# PDB.net
KiCad netlist of a schematic drawn in EAGLE
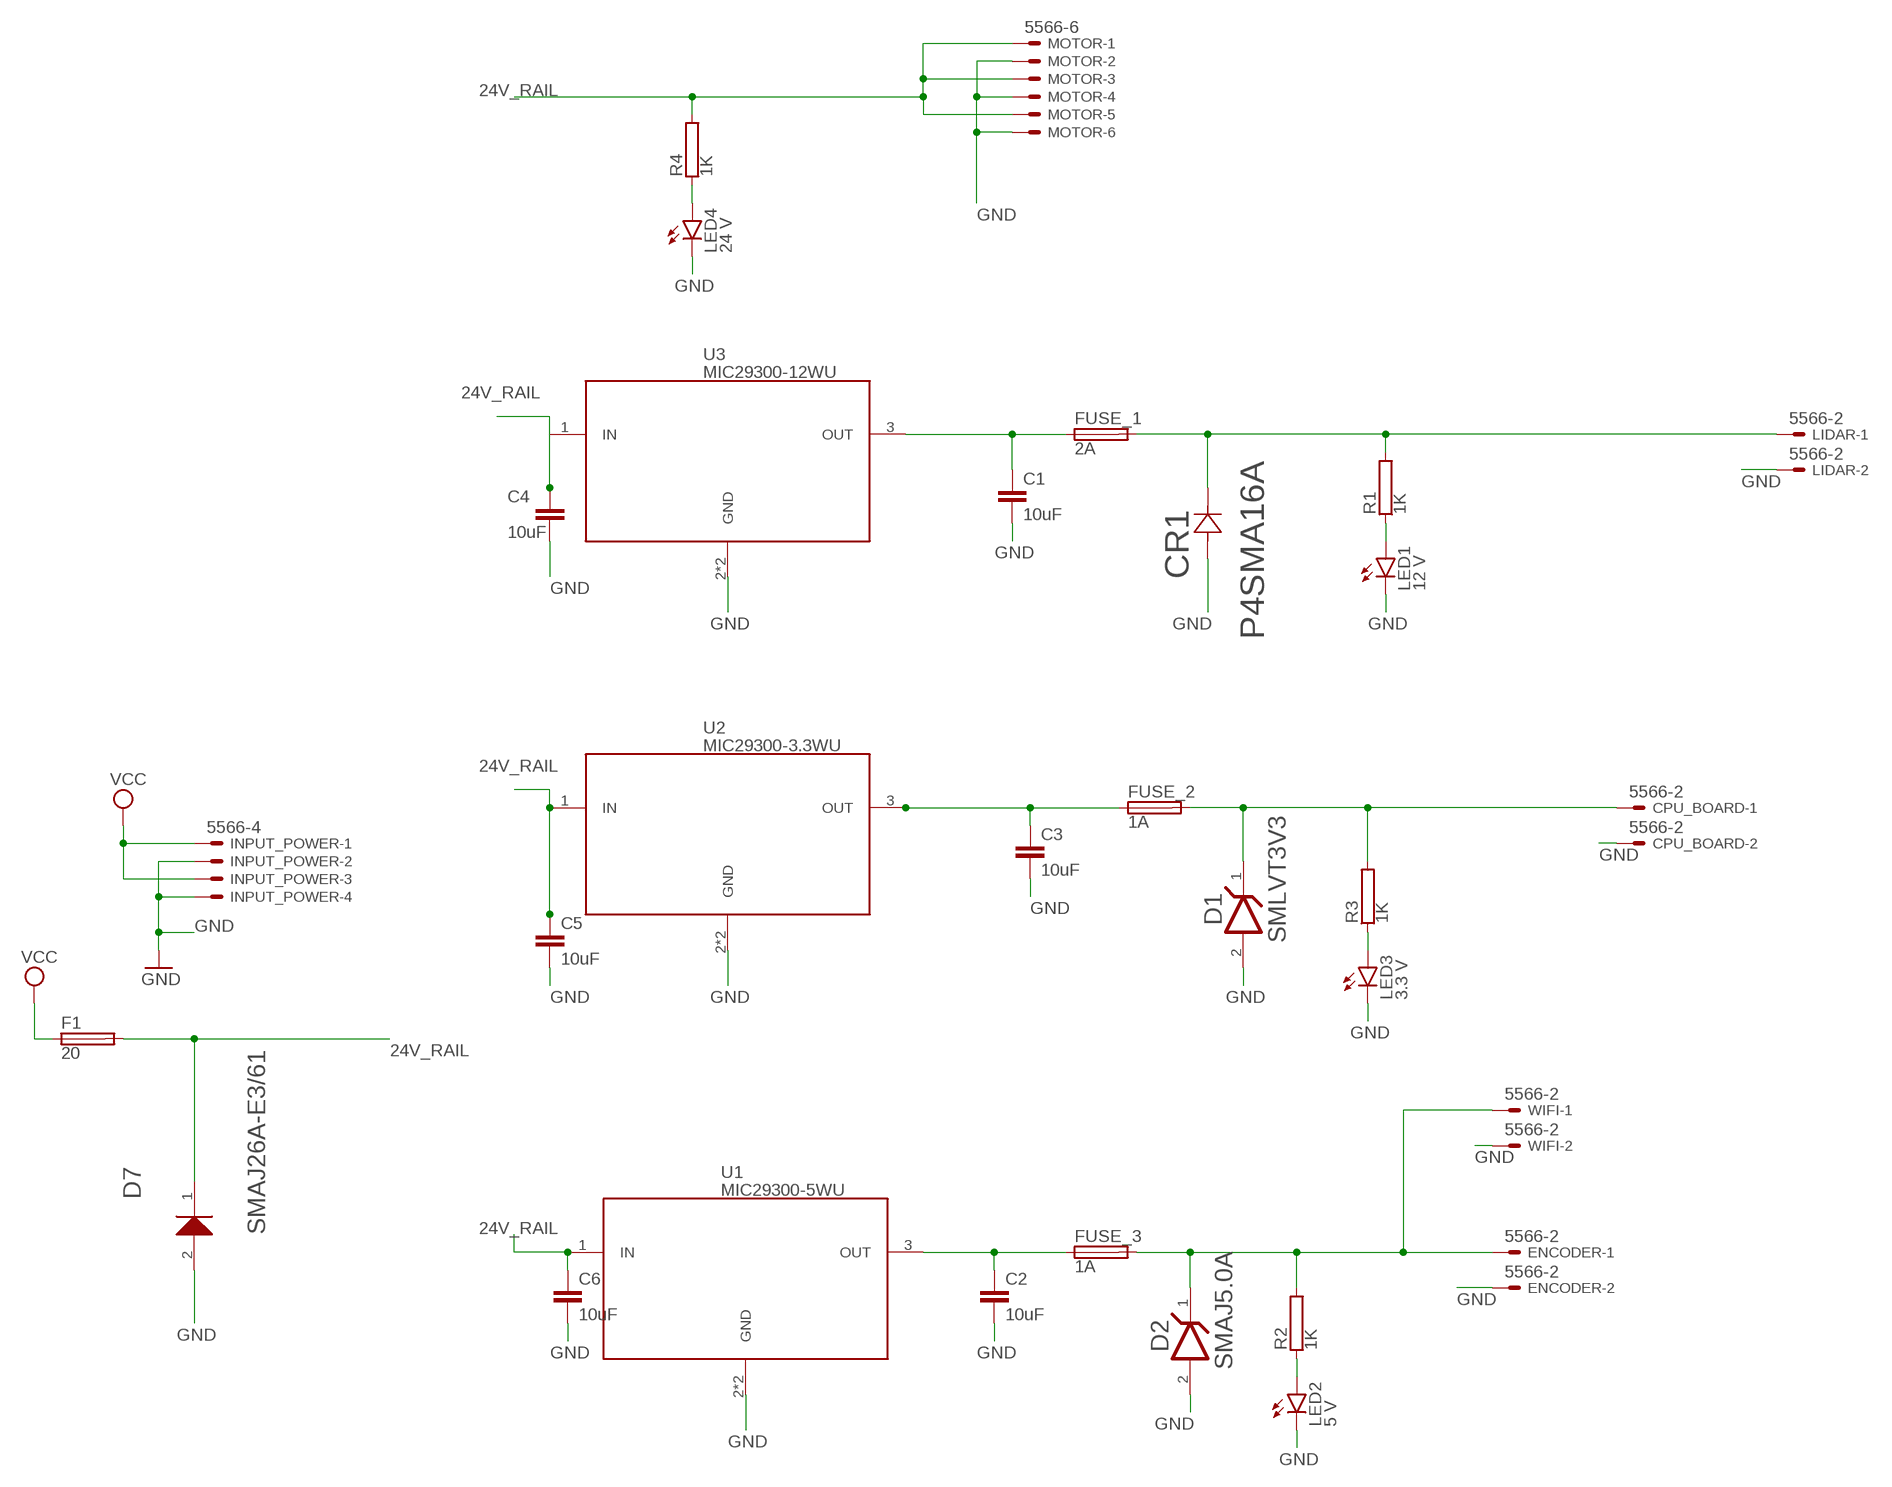
[diagram p0: schematic, sheet 1]

(export (version "E")
  (design (tool "Eeschema 10.0.6"))
  (components
    (comp (ref "C1")
      (value "10uF")
      (footprint "eagle-import:C2.5-2")
      (libsource (lib "eagle-import") (part "C2.5/2"))
    )
    (comp (ref "C2")
      (value "10uF")
      (footprint "eagle-import:C2.5-2")
      (libsource (lib "eagle-import") (part "C2.5/2"))
    )
    (comp (ref "C3")
      (value "10uF")
      (footprint "eagle-import:C2.5-2")
      (libsource (lib "eagle-import") (part "C2.5/2"))
    )
    (comp (ref "C4")
      (value "10uF")
      (footprint "eagle-import:C2.5-2")
      (libsource (lib "eagle-import") (part "C2.5/2"))
    )
    (comp (ref "C5")
      (value "10uF")
      (footprint "eagle-import:C2.5-2")
      (libsource (lib "eagle-import") (part "C2.5/2"))
    )
    (comp (ref "C6")
      (value "10uF")
      (footprint "eagle-import:C2.5-2")
      (libsource (lib "eagle-import") (part "C2.5/2"))
    )
    (comp (ref "CPU_BOARD")
      (value "5566-2")
      (footprint "eagle-import:5566-2")
      (fields (field (name "MF") "MOLEX"))
      (libsource (lib "eagle-import") (part "5566-2"))
    )
    (comp (ref "CR1")
      (value "P4SMA16A")
      (footprint "eagle-import:P4SMASERIES_LTF")
      (fields (field (name "COPYRIGHT") "Copyright (C) 2022 Ultra Librarian. All rights reserved."))
      (libsource (lib "eagle-import") (part "P4SMA16A"))
    )
    (comp (ref "D1")
      (value "STMICROELECTRONICS_SMLVT3V3STMICROELECTRONICS_SMLVT3V3_0_0")
      (footprint "eagle-import:STMICROELECTRONICS_SMLVT3V3_0")
      (fields
        (field (name "DIGIKEY_PART_NUMBER") "497-2496-1-ND")
        (field (name "MF") "STMicroelectronics")
        (field (name "MOUSER_PART_NUMBER") "511-SMLVT3V3")
      )
      (libsource (lib "eagle-import") (part "STMICROELECTRONICS_SMLVT3V3STMICROELECTRONICS_SMLVT3V3_0_0"))
    )
    (comp (ref "D2")
      (value "LITTELFUSE_INC._SMAJ5.0ALITTELFUSE_INC._SMAJ5.0A_0_0")
      (footprint "eagle-import:LITTELFUSE_INC._SMAJ5.0A_0")
      (fields
        (field (name "DIGIKEY_PART_NUMBER") "SMAJ5.0ALFCT-ND")
        (field (name "MF") "Littelfuse Inc.")
        (field (name "MOUSER_PART_NUMBER") "576-SMAJ5.0A")
      )
      (libsource (lib "eagle-import") (part "LITTELFUSE_INC._SMAJ5.0ALITTELFUSE_INC._SMAJ5.0A_0_0"))
    )
    (comp (ref "D7")
      (value "VISHAY_SEMICONDUCTOR_SMAJ26A-E3-61VISHAY_SEMICONDUCTOR_SMAJ26A-E3-61_0_0")
      (footprint "eagle-import:VISHAY_SEMICONDUCTOR_SMAJ26A-E3-61_0")
      (fields (field (name "MF") "Vishay Semiconductor") (field (name "MPN") "SMAJ26A-E3/61"))
      (libsource (lib "eagle-import") (part "VISHAY_SEMICONDUCTOR_SMAJ26A-E3-61VISHAY_SEMICONDUCTOR_SMAJ26A-E3-61_0_0"))
    )
    (comp (ref "ENCODER")
      (value "5566-2")
      (footprint "eagle-import:5566-2")
      (fields (field (name "MF") "MOLEX"))
      (libsource (lib "eagle-import") (part "5566-2"))
    )
    (comp (ref "F1")
      (value "20")
      (footprint "eagle-import:TE5")
      (libsource (lib "eagle-import") (part "TE5"))
    )
    (comp (ref "FUSE_1")
      (value "2A")
      (footprint "eagle-import:TE5")
      (libsource (lib "eagle-import") (part "TE5"))
    )
    (comp (ref "FUSE_2")
      (value "1A")
      (footprint "eagle-import:TE5")
      (libsource (lib "eagle-import") (part "TE5"))
    )
    (comp (ref "FUSE_3")
      (value "1A")
      (footprint "eagle-import:TE5")
      (libsource (lib "eagle-import") (part "TE5"))
    )
    (comp (ref "INPUT_POWER")
      (value "5566-4")
      (footprint "eagle-import:5566-4")
      (fields (field (name "MF") "MOLEX"))
      (libsource (lib "eagle-import") (part "5566-4"))
    )
    (comp (ref "LED1")
      (value "12 V")
      (footprint "eagle-import:CHIPLED_0805")
      (libsource (lib "eagle-import") (part "LEDCHIPLED_0805"))
    )
    (comp (ref "LED2")
      (value "5 V")
      (footprint "eagle-import:CHIPLED_0805")
      (libsource (lib "eagle-import") (part "LEDCHIPLED_0805"))
    )
    (comp (ref "LED3")
      (value "3.3 V")
      (footprint "eagle-import:CHIPLED_0805")
      (libsource (lib "eagle-import") (part "LEDCHIPLED_0805"))
    )
    (comp (ref "LED4")
      (value "24 V")
      (footprint "eagle-import:CHIPLED_0805")
      (libsource (lib "eagle-import") (part "LEDCHIPLED_0805"))
    )
    (comp (ref "LIDAR")
      (value "5566-2")
      (footprint "eagle-import:5566-2")
      (fields (field (name "MF") "MOLEX"))
      (libsource (lib "eagle-import") (part "5566-2"))
    )
    (comp (ref "MOTOR")
      (value "5566-6")
      (footprint "eagle-import:5566-6")
      (fields (field (name "MF") "MOLEX") (field (name "MPN") "95566-61002"))
      (libsource (lib "eagle-import") (part "5566-6"))
    )
    (comp (ref "R1")
      (value "1K")
      (footprint "eagle-import:TO-247-2V")
      (libsource (lib "eagle-import") (part "RMG100-V"))
    )
    (comp (ref "R2")
      (value "1K")
      (footprint "eagle-import:TO-247-2V")
      (libsource (lib "eagle-import") (part "RMG100-V"))
    )
    (comp (ref "R3")
      (value "1K")
      (footprint "eagle-import:TO-247-2V")
      (libsource (lib "eagle-import") (part "RMG100-V"))
    )
    (comp (ref "R4")
      (value "1K")
      (footprint "eagle-import:TO-247-2V")
      (libsource (lib "eagle-import") (part "RMG100-V"))
    )
    (comp (ref "U1")
      (value "MIC29300-5WU")
      (footprint "eagle-import:TO263")
      (fields (field (name "MF") "Microchip Technology"))
      (libsource (lib "eagle-import") (part "MIC29300-5WU"))
    )
    (comp (ref "U2")
      (value "MIC29300-3.3WU")
      (footprint "eagle-import:TO263")
      (fields (field (name "MF") "Microchip Technology"))
      (libsource (lib "eagle-import") (part "MIC29300-3.3WU"))
    )
    (comp (ref "U3")
      (value "MIC29300-12WU")
      (footprint "eagle-import:TO263")
      (fields (field (name "MF") "Microchip Technology"))
      (libsource (lib "eagle-import") (part "MIC29300-12WU"))
    )
    (comp (ref "WIFI")
      (value "5566-2")
      (footprint "eagle-import:5566-2")
      (fields (field (name "MF") "MOLEX"))
      (libsource (lib "eagle-import") (part "5566-2"))
    )
  )
  (nets
    (net (code "1") (name "/24V_RAIL") (class "Default")
      (node (ref "C4") (pin "1") (pinfunction "1_1") (pintype "passive"))
      (node (ref "C5") (pin "1") (pinfunction "1_1") (pintype "passive"))
      (node (ref "C6") (pin "1") (pinfunction "1_1") (pintype "passive"))
      (node (ref "D7") (pin "1") (pinfunction "K_1") (pintype "passive"))
      (node (ref "F1") (pin "2") (pinfunction "2_2") (pintype "passive"))
      (node (ref "MOTOR") (pin "1") (pinfunction "S_1") (pintype "passive"))
      (node (ref "MOTOR") (pin "3") (pinfunction "S_3") (pintype "passive"))
      (node (ref "MOTOR") (pin "5") (pinfunction "S_5") (pintype "passive"))
      (node (ref "R4") (pin "2") (pinfunction "2_2") (pintype "passive"))
      (node (ref "U1") (pin "1") (pinfunction "IN_1") (pintype "input"))
      (node (ref "U2") (pin "1") (pinfunction "IN_1") (pintype "input"))
      (node (ref "U3") (pin "1") (pinfunction "IN_1") (pintype "input"))
    )
    (net (code "2") (name "GND") (class "Default")
      (node (ref "C1") (pin "2") (pinfunction "2_2") (pintype "passive"))
      (node (ref "C2") (pin "2") (pinfunction "2_2") (pintype "passive"))
      (node (ref "C3") (pin "2") (pinfunction "2_2") (pintype "passive"))
      (node (ref "C4") (pin "2") (pinfunction "2_2") (pintype "passive"))
      (node (ref "C5") (pin "2") (pinfunction "2_2") (pintype "passive"))
      (node (ref "C6") (pin "2") (pinfunction "2_2") (pintype "passive"))
      (node (ref "CPU_BOARD") (pin "2") (pinfunction "S_2") (pintype "passive"))
      (node (ref "CR1") (pin "2") (pinfunction "12_2") (pintype "passive"))
      (node (ref "D1") (pin "2") (pinfunction "A_2") (pintype "passive"))
      (node (ref "D2") (pin "2") (pinfunction "ANODE_2") (pintype "passive"))
      (node (ref "D7") (pin "2") (pinfunction "A_2") (pintype "passive"))
      (node (ref "ENCODER") (pin "2") (pinfunction "S_2") (pintype "passive"))
      (node (ref "INPUT_POWER") (pin "2") (pinfunction "S_2") (pintype "passive"))
      (node (ref "INPUT_POWER") (pin "4") (pinfunction "S_4") (pintype "passive"))
      (node (ref "LED1") (pin "C") (pinfunction "C_C") (pintype "passive"))
      (node (ref "LED2") (pin "C") (pinfunction "C_C") (pintype "passive"))
      (node (ref "LED3") (pin "C") (pinfunction "C_C") (pintype "passive"))
      (node (ref "LED4") (pin "C") (pinfunction "C_C") (pintype "passive"))
      (node (ref "LIDAR") (pin "2") (pinfunction "S_2") (pintype "passive"))
      (node (ref "MOTOR") (pin "2") (pinfunction "S_2") (pintype "passive"))
      (node (ref "MOTOR") (pin "4") (pinfunction "S_4") (pintype "passive"))
      (node (ref "MOTOR") (pin "6") (pinfunction "S_6") (pintype "passive"))
      (node (ref "U1") (pin "2") (pinfunction "GND_2") (pintype "power_in"))
      (node (ref "U1") (pin "GND@") (pinfunction "GND_GND@") (pintype "power_in"))
      (node (ref "U2") (pin "2") (pinfunction "GND_2") (pintype "power_in"))
      (node (ref "U2") (pin "GND@") (pinfunction "GND_GND@") (pintype "power_in"))
      (node (ref "U3") (pin "2") (pinfunction "GND_2") (pintype "power_in"))
      (node (ref "U3") (pin "GND@") (pinfunction "GND_GND@") (pintype "power_in"))
      (node (ref "WIFI") (pin "2") (pinfunction "S_2") (pintype "passive"))
    )
    (net (code "3") (name "Net-(CPU_BOARDA-S)") (class "Default")
      (node (ref "CPU_BOARD") (pin "1") (pinfunction "S_1") (pintype "passive"))
      (node (ref "D1") (pin "1") (pinfunction "K_1") (pintype "passive"))
      (node (ref "FUSE_2") (pin "2") (pinfunction "2_2") (pintype "passive"))
      (node (ref "R3") (pin "2") (pinfunction "2_2") (pintype "passive"))
    )
    (net (code "4") (name "Net-(CR1-11)") (class "Default")
      (node (ref "CR1") (pin "1") (pinfunction "11_1") (pintype "passive"))
      (node (ref "FUSE_1") (pin "2") (pinfunction "2_2") (pintype "passive"))
      (node (ref "LIDAR") (pin "1") (pinfunction "S_1") (pintype "passive"))
      (node (ref "R1") (pin "2") (pinfunction "2_2") (pintype "passive"))
    )
    (net (code "5") (name "Net-(D2-CATHODE)") (class "Default")
      (node (ref "D2") (pin "1") (pinfunction "CATHODE_1") (pintype "passive"))
      (node (ref "ENCODER") (pin "1") (pinfunction "S_1") (pintype "passive"))
      (node (ref "FUSE_3") (pin "2") (pinfunction "2_2") (pintype "passive"))
      (node (ref "R2") (pin "2") (pinfunction "2_2") (pintype "passive"))
      (node (ref "WIFI") (pin "1") (pinfunction "S_1") (pintype "passive"))
    )
    (net (code "6") (name "Net-(LED1-PadA)") (class "Default")
      (node (ref "LED1") (pin "A") (pinfunction "A_A") (pintype "passive"))
      (node (ref "R1") (pin "1") (pinfunction "1_1") (pintype "passive"))
    )
    (net (code "7") (name "Net-(LED2-PadA)") (class "Default")
      (node (ref "LED2") (pin "A") (pinfunction "A_A") (pintype "passive"))
      (node (ref "R2") (pin "1") (pinfunction "1_1") (pintype "passive"))
    )
    (net (code "8") (name "Net-(LED3-PadA)") (class "Default")
      (node (ref "LED3") (pin "A") (pinfunction "A_A") (pintype "passive"))
      (node (ref "R3") (pin "1") (pinfunction "1_1") (pintype "passive"))
    )
    (net (code "9") (name "Net-(LED4-PadA)") (class "Default")
      (node (ref "LED4") (pin "A") (pinfunction "A_A") (pintype "passive"))
      (node (ref "R4") (pin "1") (pinfunction "1_1") (pintype "passive"))
    )
    (net (code "10") (name "Net-(U1-OUT)") (class "Default")
      (node (ref "C2") (pin "1") (pinfunction "1_1") (pintype "passive"))
      (node (ref "FUSE_3") (pin "1") (pinfunction "1_1") (pintype "passive"))
      (node (ref "U1") (pin "3") (pinfunction "OUT_3") (pintype "output"))
    )
    (net (code "11") (name "Net-(U2-OUT)") (class "Default")
      (node (ref "C3") (pin "1") (pinfunction "1_1") (pintype "passive"))
      (node (ref "FUSE_2") (pin "1") (pinfunction "1_1") (pintype "passive"))
      (node (ref "U2") (pin "3") (pinfunction "OUT_3") (pintype "output"))
    )
    (net (code "12") (name "Net-(U3-OUT)") (class "Default")
      (node (ref "C1") (pin "1") (pinfunction "1_1") (pintype "passive"))
      (node (ref "FUSE_1") (pin "1") (pinfunction "1_1") (pintype "passive"))
      (node (ref "U3") (pin "3") (pinfunction "OUT_3") (pintype "output"))
    )
    (net (code "13") (name "VCC") (class "Default")
      (node (ref "F1") (pin "1") (pinfunction "1_1") (pintype "passive"))
      (node (ref "INPUT_POWER") (pin "1") (pinfunction "S_1") (pintype "passive"))
      (node (ref "INPUT_POWER") (pin "3") (pinfunction "S_3") (pintype "passive"))
    )
  )
)
